# Amplifierschematic.net
KiCad netlist of a schematic drawn in Altium Designer
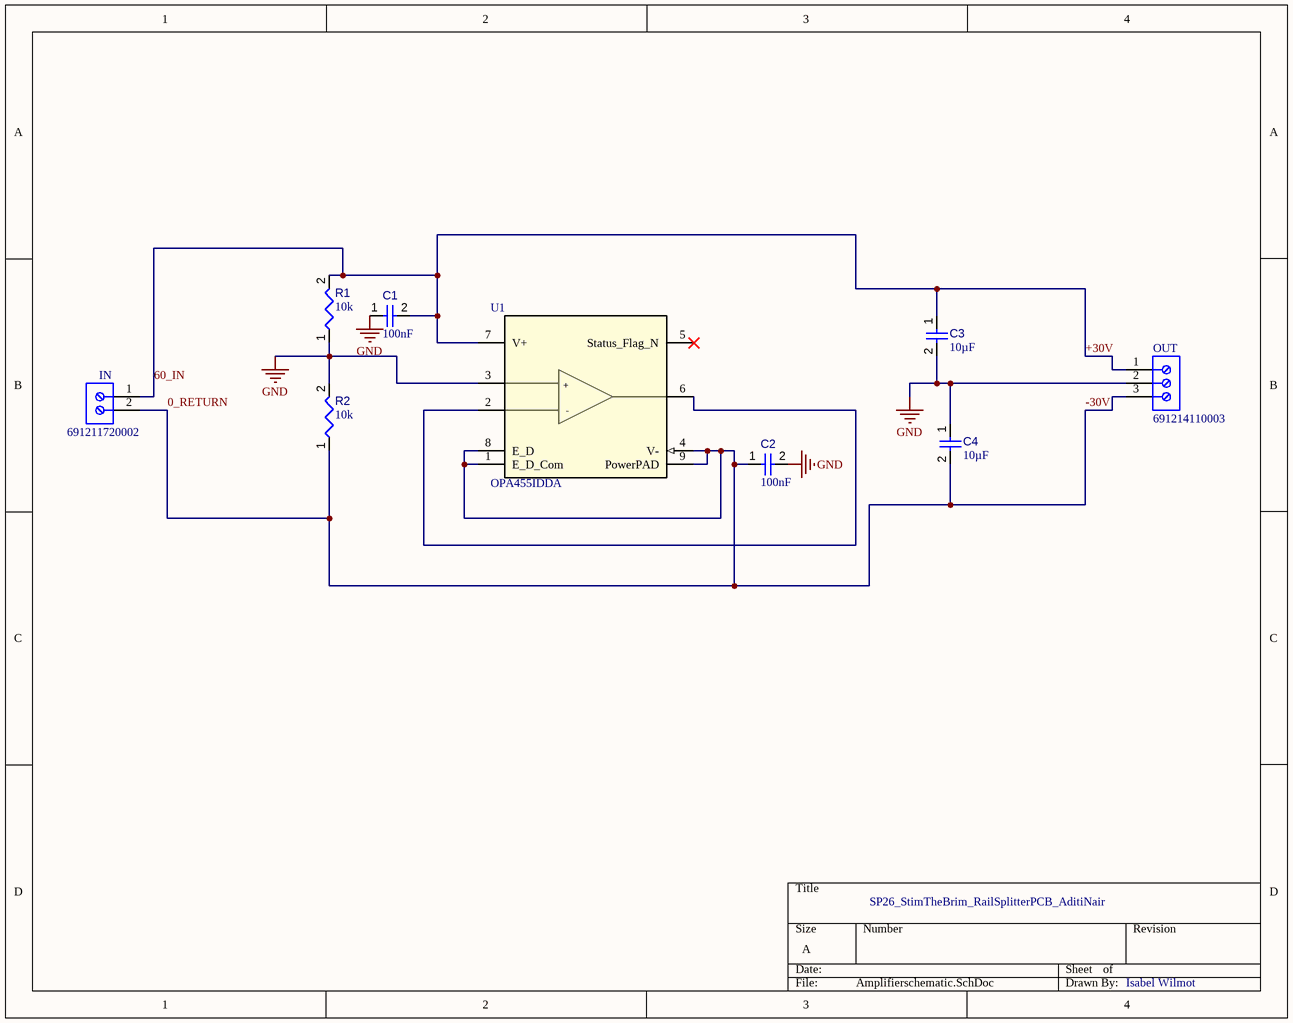
[diagram p0: Amplifierschematic.SchDoc]

(export (version "E")
  (design (tool "Eeschema 10.0.6"))
  (components
    (comp (ref "C1")
      (value "100nF")
      (footprint "CAPC0402(1005)60_L")
      (description "Chip Capacitor, 100nF +/-20%, 10V, 0402, Thickness 0.6 mm")
      (fields (field (name "TOLERANCE") "20%") (field (name "Comment") "Capacitor 100nF +/-20% 10V 0402"))
      (libsource (lib "Aditi Nair") (part "CAP-NP-2"))
    )
    (comp (ref "C2")
      (value "100nF")
      (footprint "CAPC0402(1005)60_L")
      (description "Chip Capacitor, 100nF +/-20%, 10V, 0402, Thickness 0.6 mm")
      (fields (field (name "TOLERANCE") "20%") (field (name "Comment") "Capacitor 100nF +/-20% 10V 0402"))
      (libsource (lib "Aditi Nair") (part "CAP-NP-2"))
    )
    (comp (ref "C3")
      (value "10µF")
      (footprint "CAPC0603(1608)100_L")
      (description "Chip Capacitor, 10µF +/-20%, 10V, 0603, Thickness 1 mm")
      (fields (field (name "TOLERANCE") "10%") (field (name "Comment") "Capacitor 10µF +/-20% 10V 0603"))
      (libsource (lib "Aditi Nair") (part "CAP-NP-2"))
    )
    (comp (ref "C4")
      (value "10µF")
      (footprint "CAPC0603(1608)100_L")
      (description "Chip Capacitor, 10µF +/-20%, 10V, 0603, Thickness 1 mm")
      (fields (field (name "TOLERANCE") "10%") (field (name "Comment") "Capacitor 10µF +/-20% 10V 0603"))
      (libsource (lib "Aditi Nair") (part "CAP-NP-2"))
    )
    (comp (ref "IN")
      (value "691211720002")
      (footprint "691211720002")
      (description "211 Series 5MM Pitch Straight, Pcb Terminal Block, Through Hole, 2 Way")
      (fields (field (name "VOLTAGE") "300V"))
      (libsource (lib "Altium Content Vault") (part "TBL - 1R - 02P - Screw"))
    )
    (comp (ref "OUT")
      (value "691214110003")
      (footprint "691214110003")
      (description "2141 Series 3.5MM Pitch Straight, Pcb Terminal Block, Through Hole, 3 Way")
      (fields (field (name "VOLTAGE") "300V"))
      (libsource (lib "Altium Content Vault") (part "TBL - 1R - 03P - Screw"))
    )
    (comp (ref "R1")
      (value "10k")
      (footprint "RESC1005X40X25ML05T05")
      (description "Chip Resistor, 10 KOhm, +/- 1%, 0.1 W, -55 to 155 degC, 0402 (1005 Metric)")
      (fields (field (name "POWER") "100mW") (field (name "TOLERANCE") "1%"))
      (libsource (lib "Aditi Nair") (part "RES-2"))
    )
    (comp (ref "R2")
      (value "10k")
      (footprint "RESC1005X40X25ML05T05")
      (description "Chip Resistor, 10 KOhm, +/- 1%, 0.1 W, -55 to 155 degC, 0402 (1005 Metric)")
      (fields (field (name "POWER") "100mW") (field (name "TOLERANCE") "1%"))
      (libsource (lib "Aditi Nair") (part "RES-2"))
    )
    (comp (ref "U1")
      (value "OPA455IDDA")
      (footprint "DDA0008J-IPC_A")
      (fields (field (name "COPYRIGHT") "Copyright (C) 2026 Ultra Librarian. All rights reserved."))
      (libsource (lib "OPA455IDDA") (part "OPA455IDDA"))
    )
  )
  (nets
    (net (code "1") (name "/+30V") (class "Default")
      (node (ref "C1") (pin "2") (pinfunction "2_2") (pintype "passive"))
      (node (ref "C3") (pin "1") (pinfunction "1_1") (pintype "passive"))
      (node (ref "IN") (pin "1") (pinfunction "1_1") (pintype "passive"))
      (node (ref "OUT") (pin "1") (pinfunction "1_1") (pintype "passive"))
      (node (ref "R1") (pin "2") (pinfunction "2_2") (pintype "passive"))
      (node (ref "U1") (pin "7") (pinfunction "V+_7") (pintype "power_in"))
    )
    (net (code "2") (name "/-30V") (class "Default")
      (node (ref "C2") (pin "1") (pinfunction "1_1") (pintype "passive"))
      (node (ref "C4") (pin "2") (pinfunction "2_2") (pintype "passive"))
      (node (ref "IN") (pin "2") (pinfunction "2_2") (pintype "passive"))
      (node (ref "OUT") (pin "3") (pinfunction "3_3") (pintype "passive"))
      (node (ref "R2") (pin "1") (pinfunction "1_1") (pintype "passive"))
      (node (ref "U1") (pin "1") (pinfunction "E_D_Com_1") (pintype "passive"))
      (node (ref "U1") (pin "4") (pinfunction "V-_4") (pintype "input"))
      (node (ref "U1") (pin "8") (pinfunction "E_D_8") (pintype "open_collector"))
      (node (ref "U1") (pin "9") (pinfunction "PowerPAD_9") (pintype "passive"))
    )
    (net (code "3") (name "GND") (class "Default")
      (node (ref "C1") (pin "1") (pinfunction "1_1") (pintype "passive"))
      (node (ref "C2") (pin "2") (pinfunction "2_2") (pintype "passive"))
      (node (ref "C3") (pin "2") (pinfunction "2_2") (pintype "passive"))
      (node (ref "C4") (pin "1") (pinfunction "1_1") (pintype "passive"))
      (node (ref "OUT") (pin "2") (pinfunction "2_2") (pintype "passive"))
      (node (ref "R1") (pin "1") (pinfunction "1_1") (pintype "passive"))
      (node (ref "R2") (pin "2") (pinfunction "2_2") (pintype "passive"))
      (node (ref "U1") (pin "3") (pinfunction "+IN_3") (pintype "passive"))
    )
    (net (code "4") (name "Net-(U1--IN)") (class "Default")
      (node (ref "U1") (pin "2") (pinfunction "-IN_2") (pintype "passive"))
      (node (ref "U1") (pin "6") (pinfunction "OUT_6") (pintype "tri_state"))
    )
    (net (code "5") (name "unconnected-(U1-Status_Flag_N-Pad5)") (class "Default")
      (node (ref "U1") (pin "5") (pinfunction "Status_Flag_N_5") (pintype "tri_state+no_connect"))
    )
  )
)
